# moids2_0_1.net
KiCad netlist of a schematic drawn in EAGLE
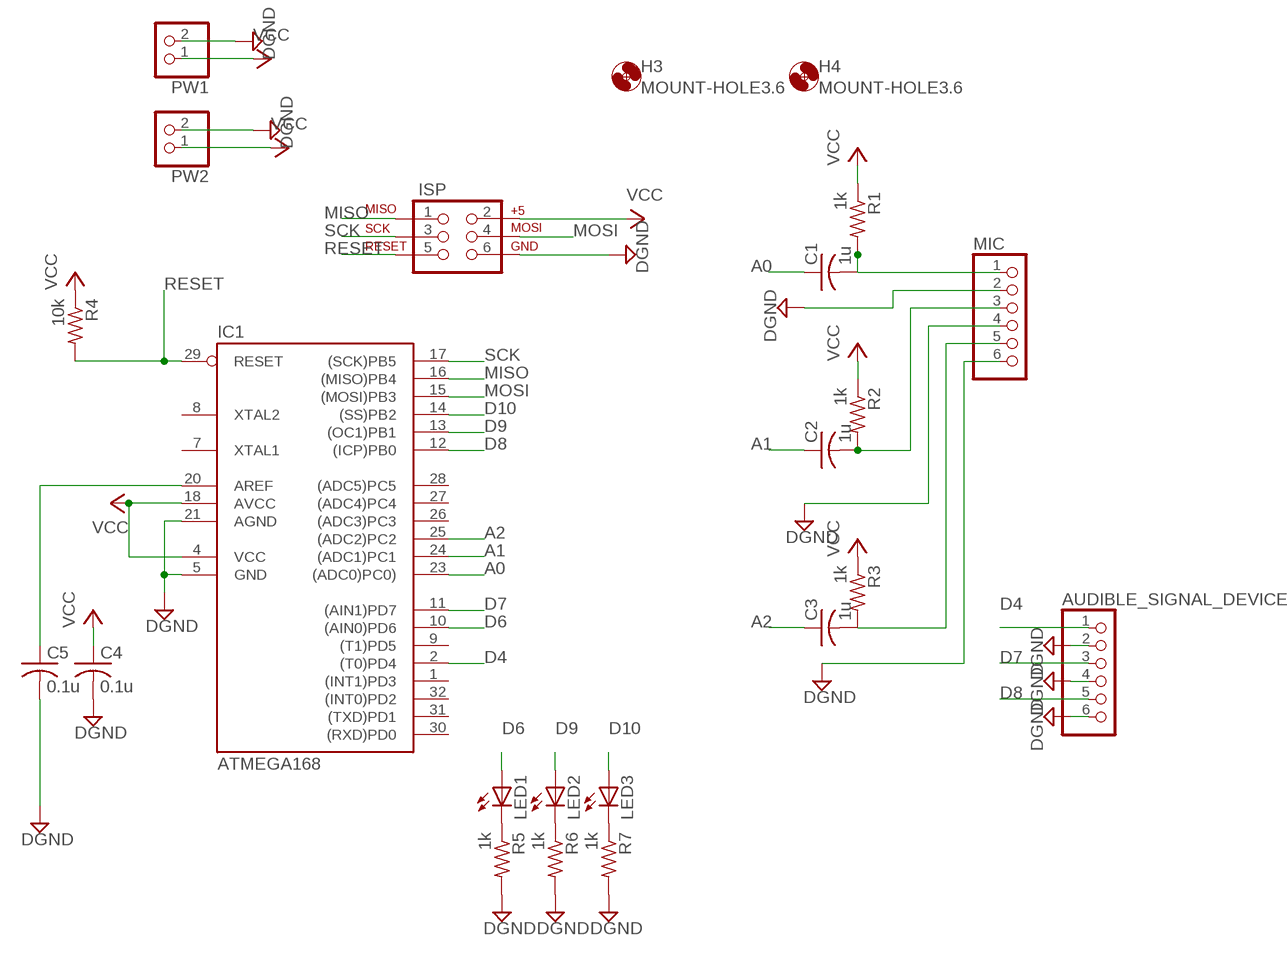
[diagram p0: schematic, sheet 1]

(export (version "E")
  (design (tool "Eeschema 10.0.6"))
  (components
    (comp (ref "AUDIBLE_SIGNAL_DEVICE")
      (value "PINHD-1X6")
      (footprint "eagle-import:1X06")
      (libsource (lib "eagle-import") (part "PINHD-1X6"))
    )
    (comp (ref "C1")
      (value "1u")
      (footprint "eagle-import:C1005")
      (libsource (lib "eagle-import") (part "C-USC1005"))
    )
    (comp (ref "C2")
      (value "1u")
      (footprint "eagle-import:C1005")
      (libsource (lib "eagle-import") (part "C-USC1005"))
    )
    (comp (ref "C3")
      (value "1u")
      (footprint "eagle-import:C1005")
      (libsource (lib "eagle-import") (part "C-USC1005"))
    )
    (comp (ref "C4")
      (value "0.1u")
      (footprint "eagle-import:C1005")
      (libsource (lib "eagle-import") (part "C-USC1005"))
    )
    (comp (ref "C5")
      (value "0.1u")
      (footprint "eagle-import:C1005")
      (libsource (lib "eagle-import") (part "C-USC1005"))
    )
    (comp (ref "H3")
      (value "MOUNT-HOLE3.6")
      (footprint "eagle-import:3,6")
      (libsource (lib "eagle-import") (part "MOUNT-HOLE3.6"))
    )
    (comp (ref "H4")
      (value "MOUNT-HOLE3.6")
      (footprint "eagle-import:3,6")
      (libsource (lib "eagle-import") (part "MOUNT-HOLE3.6"))
    )
    (comp (ref "IC1")
      (value "ATMEGA168")
      (footprint "eagle-import:TQFP32-08")
      (libsource (lib "eagle-import") (part "AT90S4433A"))
    )
    (comp (ref "ISP")
      (value "AVR_SPI_PRG_6PTH")
      (footprint "eagle-import:2X3")
      (libsource (lib "eagle-import") (part "AVR_SPI_PRG_6PTH"))
    )
    (comp (ref "LED1")
      (value "LEDCHIPLED_1206")
      (footprint "eagle-import:CHIPLED_1206")
      (libsource (lib "eagle-import") (part "LEDCHIPLED_1206"))
    )
    (comp (ref "LED2")
      (value "LEDCHIPLED_1206")
      (footprint "eagle-import:CHIPLED_1206")
      (libsource (lib "eagle-import") (part "LEDCHIPLED_1206"))
    )
    (comp (ref "LED3")
      (value "LEDCHIPLED_1206")
      (footprint "eagle-import:CHIPLED_1206")
      (libsource (lib "eagle-import") (part "LEDCHIPLED_1206"))
    )
    (comp (ref "MIC")
      (value "PINHD-1X6")
      (footprint "eagle-import:1X06")
      (libsource (lib "eagle-import") (part "PINHD-1X6"))
    )
    (comp (ref "PW1")
      (value "PINHD-1X2")
      (footprint "eagle-import:1X02")
      (libsource (lib "eagle-import") (part "PINHD-1X2"))
    )
    (comp (ref "PW2")
      (value "PINHD-1X2")
      (footprint "eagle-import:1X02")
      (libsource (lib "eagle-import") (part "PINHD-1X2"))
    )
    (comp (ref "R1")
      (value "1k")
      (footprint "eagle-import:R1005")
      (libsource (lib "eagle-import") (part "R-US_R1005"))
    )
    (comp (ref "R2")
      (value "1k")
      (footprint "eagle-import:R1005")
      (libsource (lib "eagle-import") (part "R-US_R1005"))
    )
    (comp (ref "R3")
      (value "1k")
      (footprint "eagle-import:R1005")
      (libsource (lib "eagle-import") (part "R-US_R1005"))
    )
    (comp (ref "R4")
      (value "10k")
      (footprint "eagle-import:R1005")
      (libsource (lib "eagle-import") (part "R-US_R1005"))
    )
    (comp (ref "R5")
      (value "1k")
      (footprint "eagle-import:R1005")
      (libsource (lib "eagle-import") (part "R-US_R1005"))
    )
    (comp (ref "R6")
      (value "1k")
      (footprint "eagle-import:R1005")
      (libsource (lib "eagle-import") (part "R-US_R1005"))
    )
    (comp (ref "R7")
      (value "1k")
      (footprint "eagle-import:R1005")
      (libsource (lib "eagle-import") (part "R-US_R1005"))
    )
  )
  (nets
    (net (code "1") (name "/A0") (class "Default")
      (node (ref "C1") (pin "1") (pinfunction "1_1") (pintype "passive"))
      (node (ref "IC1") (pin "23") (pinfunction "(ADC0)PC0)_23") (pintype "bidirectional"))
    )
    (net (code "2") (name "/A1") (class "Default")
      (node (ref "C2") (pin "1") (pinfunction "1_1") (pintype "passive"))
      (node (ref "IC1") (pin "24") (pinfunction "(ADC1)PC1_24") (pintype "bidirectional"))
    )
    (net (code "3") (name "/A2") (class "Default")
      (node (ref "C3") (pin "1") (pinfunction "1_1") (pintype "passive"))
      (node (ref "IC1") (pin "25") (pinfunction "(ADC2)PC2_25") (pintype "bidirectional"))
    )
    (net (code "4") (name "/D4") (class "Default")
      (node (ref "AUDIBLE_SIGNAL_DEVICE") (pin "1") (pinfunction "1_1") (pintype "passive"))
      (node (ref "IC1") (pin "2") (pinfunction "(T0)PD4_2") (pintype "bidirectional"))
    )
    (net (code "5") (name "/D6") (class "Default")
      (node (ref "IC1") (pin "10") (pinfunction "(AIN0)PD6_10") (pintype "bidirectional"))
      (node (ref "LED1") (pin "A") (pinfunction "A_A") (pintype "passive"))
    )
    (net (code "6") (name "/D7") (class "Default")
      (node (ref "AUDIBLE_SIGNAL_DEVICE") (pin "3") (pinfunction "3_3") (pintype "passive"))
      (node (ref "IC1") (pin "11") (pinfunction "(AIN1)PD7_11") (pintype "bidirectional"))
    )
    (net (code "7") (name "/D8") (class "Default")
      (node (ref "AUDIBLE_SIGNAL_DEVICE") (pin "5") (pinfunction "5_5") (pintype "passive"))
      (node (ref "IC1") (pin "12") (pinfunction "(ICP)PB0_12") (pintype "bidirectional"))
    )
    (net (code "8") (name "/D9") (class "Default")
      (node (ref "IC1") (pin "13") (pinfunction "(OC1)PB1_13") (pintype "bidirectional"))
      (node (ref "LED2") (pin "A") (pinfunction "A_A") (pintype "passive"))
    )
    (net (code "9") (name "/D10") (class "Default")
      (node (ref "IC1") (pin "14") (pinfunction "(SS)PB2_14") (pintype "bidirectional"))
      (node (ref "LED3") (pin "A") (pinfunction "A_A") (pintype "passive"))
    )
    (net (code "10") (name "/MISO") (class "Default")
      (node (ref "IC1") (pin "16") (pinfunction "(MISO)PB4_16") (pintype "bidirectional"))
      (node (ref "ISP") (pin "1") (pinfunction "1_1") (pintype "passive"))
    )
    (net (code "11") (name "/MOSI") (class "Default")
      (node (ref "IC1") (pin "15") (pinfunction "(MOSI)PB3_15") (pintype "bidirectional"))
      (node (ref "ISP") (pin "4") (pinfunction "4_4") (pintype "passive"))
    )
    (net (code "12") (name "/RESET") (class "Default")
      (node (ref "IC1") (pin "29") (pinfunction "RESET_29") (pintype "input"))
      (node (ref "ISP") (pin "5") (pinfunction "5_5") (pintype "passive"))
      (node (ref "R4") (pin "2") (pinfunction "2_2") (pintype "passive"))
    )
    (net (code "13") (name "/SCK") (class "Default")
      (node (ref "IC1") (pin "17") (pinfunction "(SCK)PB5_17") (pintype "bidirectional"))
      (node (ref "ISP") (pin "3") (pinfunction "3_3") (pintype "passive"))
    )
    (net (code "14") (name "DGND") (class "Default")
      (node (ref "AUDIBLE_SIGNAL_DEVICE") (pin "2") (pinfunction "2_2") (pintype "passive"))
      (node (ref "AUDIBLE_SIGNAL_DEVICE") (pin "4") (pinfunction "4_4") (pintype "passive"))
      (node (ref "AUDIBLE_SIGNAL_DEVICE") (pin "6") (pinfunction "6_6") (pintype "passive"))
      (node (ref "C4") (pin "2") (pinfunction "2_2") (pintype "passive"))
      (node (ref "C5") (pin "2") (pinfunction "2_2") (pintype "passive"))
      (node (ref "IC1") (pin "21") (pinfunction "AGND_21") (pintype "power_in"))
      (node (ref "IC1") (pin "5") (pinfunction "GND_5") (pintype "power_in"))
      (node (ref "ISP") (pin "6") (pinfunction "6_6") (pintype "passive"))
      (node (ref "MIC") (pin "2") (pinfunction "2_2") (pintype "passive"))
      (node (ref "MIC") (pin "4") (pinfunction "4_4") (pintype "passive"))
      (node (ref "MIC") (pin "6") (pinfunction "6_6") (pintype "passive"))
      (node (ref "PW1") (pin "2") (pinfunction "2_2") (pintype "passive"))
      (node (ref "PW2") (pin "2") (pinfunction "2_2") (pintype "passive"))
      (node (ref "R5") (pin "2") (pinfunction "2_2") (pintype "passive"))
      (node (ref "R6") (pin "2") (pinfunction "2_2") (pintype "passive"))
      (node (ref "R7") (pin "2") (pinfunction "2_2") (pintype "passive"))
    )
    (net (code "15") (name "Net-(C1-Pad2)") (class "Default")
      (node (ref "C1") (pin "2") (pinfunction "2_2") (pintype "passive"))
      (node (ref "MIC") (pin "1") (pinfunction "1_1") (pintype "passive"))
      (node (ref "R1") (pin "2") (pinfunction "2_2") (pintype "passive"))
    )
    (net (code "16") (name "Net-(C2-Pad2)") (class "Default")
      (node (ref "C2") (pin "2") (pinfunction "2_2") (pintype "passive"))
      (node (ref "MIC") (pin "3") (pinfunction "3_3") (pintype "passive"))
      (node (ref "R2") (pin "2") (pinfunction "2_2") (pintype "passive"))
    )
    (net (code "17") (name "Net-(C3-Pad2)") (class "Default")
      (node (ref "C3") (pin "2") (pinfunction "2_2") (pintype "passive"))
      (node (ref "MIC") (pin "5") (pinfunction "5_5") (pintype "passive"))
      (node (ref "R3") (pin "2") (pinfunction "2_2") (pintype "passive"))
    )
    (net (code "18") (name "Net-(IC1-AREF)") (class "Default")
      (node (ref "C5") (pin "1") (pinfunction "1_1") (pintype "passive"))
      (node (ref "IC1") (pin "20") (pinfunction "AREF_20") (pintype "passive"))
    )
    (net (code "19") (name "Net-(LED1-PadC)") (class "Default")
      (node (ref "LED1") (pin "C") (pinfunction "C_C") (pintype "passive"))
      (node (ref "R5") (pin "1") (pinfunction "1_1") (pintype "passive"))
    )
    (net (code "20") (name "Net-(LED2-PadC)") (class "Default")
      (node (ref "LED2") (pin "C") (pinfunction "C_C") (pintype "passive"))
      (node (ref "R6") (pin "1") (pinfunction "1_1") (pintype "passive"))
    )
    (net (code "21") (name "Net-(LED3-PadC)") (class "Default")
      (node (ref "LED3") (pin "C") (pinfunction "C_C") (pintype "passive"))
      (node (ref "R7") (pin "1") (pinfunction "1_1") (pintype "passive"))
    )
    (net (code "22") (name "VCC") (class "Default")
      (node (ref "C4") (pin "1") (pinfunction "1_1") (pintype "passive"))
      (node (ref "IC1") (pin "18") (pinfunction "AVCC_18") (pintype "power_in"))
      (node (ref "IC1") (pin "4") (pinfunction "VCC_4") (pintype "power_in"))
      (node (ref "ISP") (pin "2") (pinfunction "2_2") (pintype "passive"))
      (node (ref "PW1") (pin "1") (pinfunction "1_1") (pintype "passive"))
      (node (ref "PW2") (pin "1") (pinfunction "1_1") (pintype "passive"))
      (node (ref "R1") (pin "1") (pinfunction "1_1") (pintype "passive"))
      (node (ref "R2") (pin "1") (pinfunction "1_1") (pintype "passive"))
      (node (ref "R3") (pin "1") (pinfunction "1_1") (pintype "passive"))
      (node (ref "R4") (pin "1") (pinfunction "1_1") (pintype "passive"))
    )
    (net (code "23") (name "unconnected-(IC1-(ADC3)PC3-Pad26)") (class "Default")
      (node (ref "IC1") (pin "26") (pinfunction "(ADC3)PC3_26") (pintype "bidirectional"))
    )
    (net (code "24") (name "unconnected-(IC1-(ADC4)PC4-Pad27)") (class "Default")
      (node (ref "IC1") (pin "27") (pinfunction "(ADC4)PC4_27") (pintype "bidirectional"))
    )
    (net (code "25") (name "unconnected-(IC1-(ADC5)PC5-Pad28)") (class "Default")
      (node (ref "IC1") (pin "28") (pinfunction "(ADC5)PC5_28") (pintype "bidirectional"))
    )
    (net (code "26") (name "unconnected-(IC1-(INT0)PD2-Pad32)") (class "Default")
      (node (ref "IC1") (pin "32") (pinfunction "(INT0)PD2_32") (pintype "bidirectional"))
    )
    (net (code "27") (name "unconnected-(IC1-(INT1)PD3-Pad1)") (class "Default")
      (node (ref "IC1") (pin "1") (pinfunction "(INT1)PD3_1") (pintype "bidirectional"))
    )
    (net (code "28") (name "unconnected-(IC1-(RXD)PD0-Pad30)") (class "Default")
      (node (ref "IC1") (pin "30") (pinfunction "(RXD)PD0_30") (pintype "bidirectional"))
    )
    (net (code "29") (name "unconnected-(IC1-(T1)PD5-Pad9)") (class "Default")
      (node (ref "IC1") (pin "9") (pinfunction "(T1)PD5_9") (pintype "bidirectional"))
    )
    (net (code "30") (name "unconnected-(IC1-(TXD)PD1-Pad31)") (class "Default")
      (node (ref "IC1") (pin "31") (pinfunction "(TXD)PD1_31") (pintype "bidirectional"))
    )
    (net (code "31") (name "unconnected-(IC1-XTAL1-Pad7)") (class "Default")
      (node (ref "IC1") (pin "7") (pinfunction "XTAL1_7") (pintype "bidirectional"))
    )
    (net (code "32") (name "unconnected-(IC1-XTAL2-Pad8)") (class "Default")
      (node (ref "IC1") (pin "8") (pinfunction "XTAL2_8") (pintype "bidirectional"))
    )
  )
)
